# ExpBoard1.net
KiCad netlist of a schematic drawn in EAGLE
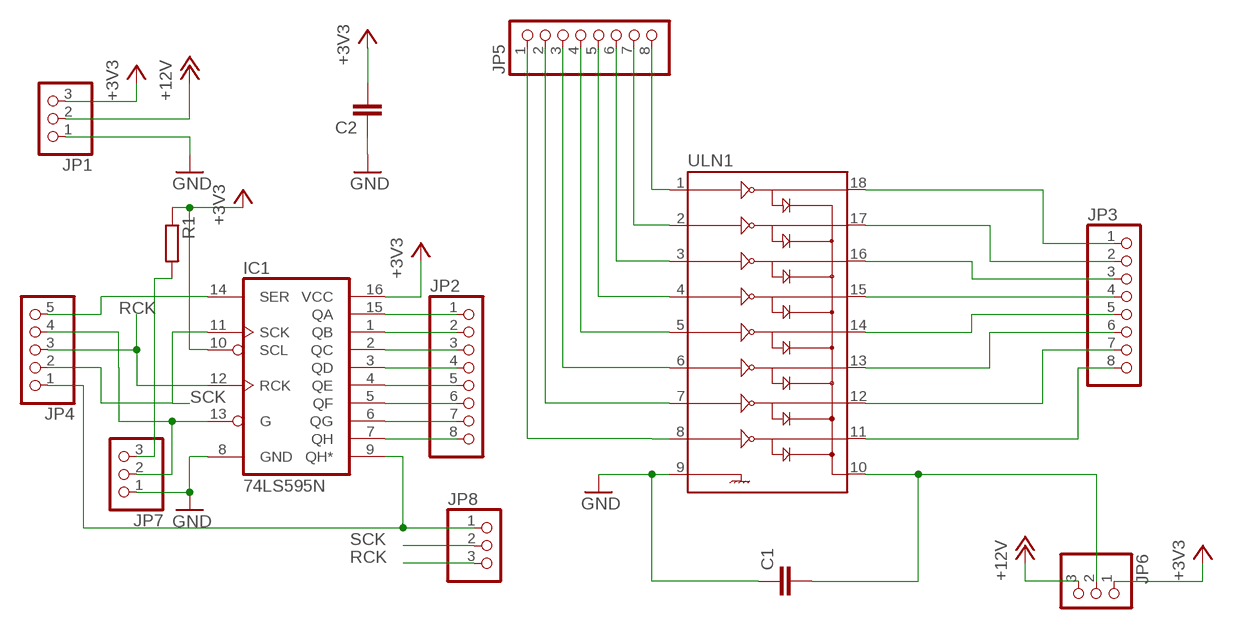
[diagram p0: schematic, sheet 1]

(export (version "E")
  (design (tool "Eeschema 10.0.6"))
  (components
    (comp (ref "C1")
      (value "C-EU050-024X044")
      (footprint "eagle-import:C050-024X044")
      (libsource (lib "eagle-import") (part "C-EU050-024X044"))
    )
    (comp (ref "C2")
      (value "C-EU025-024X044")
      (footprint "eagle-import:C025-024X044")
      (libsource (lib "eagle-import") (part "C-EU025-024X044"))
    )
    (comp (ref "IC1")
      (value "74LS595N")
      (footprint "eagle-import:DIL16")
      (libsource (lib "eagle-import") (part "74595NLS"))
    )
    (comp (ref "JP1")
      (value "PINHD-1X3")
      (footprint "eagle-import:1X03")
      (libsource (lib "eagle-import") (part "PINHD-1X3"))
    )
    (comp (ref "JP2")
      (value "PINHD-1X8")
      (footprint "eagle-import:1X08")
      (libsource (lib "eagle-import") (part "PINHD-1X8"))
    )
    (comp (ref "JP3")
      (value "PINHD-1X8")
      (footprint "eagle-import:1X08")
      (libsource (lib "eagle-import") (part "PINHD-1X8"))
    )
    (comp (ref "JP4")
      (value "PINHD-1X5")
      (footprint "eagle-import:1X05")
      (libsource (lib "eagle-import") (part "PINHD-1X5"))
    )
    (comp (ref "JP5")
      (value "PINHD-1X8")
      (footprint "eagle-import:1X08")
      (libsource (lib "eagle-import") (part "PINHD-1X8"))
    )
    (comp (ref "JP6")
      (value "PINHD-1X3")
      (footprint "eagle-import:1X03")
      (libsource (lib "eagle-import") (part "PINHD-1X3"))
    )
    (comp (ref "JP7")
      (value "PINHD-1X3")
      (footprint "eagle-import:1X03")
      (libsource (lib "eagle-import") (part "PINHD-1X3"))
    )
    (comp (ref "JP8")
      (value "PINHD-1X3")
      (footprint "eagle-import:1X03")
      (libsource (lib "eagle-import") (part "PINHD-1X3"))
    )
    (comp (ref "R1")
      (value "R-EU_0207/12")
      (footprint "eagle-import:0207_12")
      (libsource (lib "eagle-import") (part "R-EU_0207/12"))
    )
    (comp (ref "ULN1")
      (value "ULN2803DIP")
      (footprint "eagle-import:DIL18")
      (libsource (lib "eagle-import") (part "ULN2803DIP"))
    )
  )
  (nets
    (net (code "1") (name "+3V3") (class "Default")
      (node (ref "C2") (pin "2") (pinfunction "2_2") (pintype "passive"))
      (node (ref "IC1") (pin "10") (pinfunction "SCL_10") (pintype "input"))
      (node (ref "IC1") (pin "16") (pinfunction "VCC_16") (pintype "power_in"))
      (node (ref "JP1") (pin "3") (pinfunction "3_3") (pintype "passive"))
      (node (ref "JP6") (pin "1") (pinfunction "1_1") (pintype "passive"))
      (node (ref "R1") (pin "1") (pinfunction "1_1") (pintype "passive"))
    )
    (net (code "2") (name "+12V") (class "Default")
      (node (ref "JP1") (pin "2") (pinfunction "2_2") (pintype "passive"))
      (node (ref "JP6") (pin "3") (pinfunction "3_3") (pintype "passive"))
    )
    (net (code "3") (name "/RCK") (class "Default")
      (node (ref "IC1") (pin "12") (pinfunction "RCK_12") (pintype "input"))
      (node (ref "JP4") (pin "3") (pinfunction "3_3") (pintype "passive"))
      (node (ref "JP8") (pin "3") (pinfunction "3_3") (pintype "passive"))
    )
    (net (code "4") (name "/SCK") (class "Default")
      (node (ref "IC1") (pin "11") (pinfunction "SCK_11") (pintype "input"))
      (node (ref "JP4") (pin "2") (pinfunction "2_2") (pintype "passive"))
      (node (ref "JP8") (pin "2") (pinfunction "2_2") (pintype "passive"))
    )
    (net (code "5") (name "GND") (class "Default")
      (node (ref "C1") (pin "1") (pinfunction "1_1") (pintype "passive"))
      (node (ref "C2") (pin "1") (pinfunction "1_1") (pintype "passive"))
      (node (ref "IC1") (pin "8") (pinfunction "GND_8") (pintype "power_in"))
      (node (ref "JP1") (pin "1") (pinfunction "1_1") (pintype "passive"))
      (node (ref "JP7") (pin "1") (pinfunction "1_1") (pintype "passive"))
      (node (ref "ULN1") (pin "9") (pinfunction "9_9") (pintype "bidirectional"))
    )
    (net (code "6") (name "Net-(C1-Pad2)") (class "Default")
      (node (ref "C1") (pin "2") (pinfunction "2_2") (pintype "passive"))
      (node (ref "JP6") (pin "2") (pinfunction "2_2") (pintype "passive"))
      (node (ref "ULN1") (pin "10") (pinfunction "10_10") (pintype "bidirectional"))
    )
    (net (code "7") (name "Net-(IC1-G)") (class "Default")
      (node (ref "IC1") (pin "13") (pinfunction "G_13") (pintype "input"))
      (node (ref "JP4") (pin "4") (pinfunction "4_4") (pintype "passive"))
      (node (ref "JP7") (pin "2") (pinfunction "2_2") (pintype "passive"))
    )
    (net (code "8") (name "Net-(IC1-QA)") (class "Default")
      (node (ref "IC1") (pin "15") (pinfunction "QA_15") (pintype "tri_state"))
      (node (ref "JP2") (pin "1") (pinfunction "1_1") (pintype "passive"))
    )
    (net (code "9") (name "Net-(IC1-QB)") (class "Default")
      (node (ref "IC1") (pin "1") (pinfunction "QB_1") (pintype "tri_state"))
      (node (ref "JP2") (pin "2") (pinfunction "2_2") (pintype "passive"))
    )
    (net (code "10") (name "Net-(IC1-QC)") (class "Default")
      (node (ref "IC1") (pin "2") (pinfunction "QC_2") (pintype "tri_state"))
      (node (ref "JP2") (pin "3") (pinfunction "3_3") (pintype "passive"))
    )
    (net (code "11") (name "Net-(IC1-QD)") (class "Default")
      (node (ref "IC1") (pin "3") (pinfunction "QD_3") (pintype "tri_state"))
      (node (ref "JP2") (pin "4") (pinfunction "4_4") (pintype "passive"))
    )
    (net (code "12") (name "Net-(IC1-QE)") (class "Default")
      (node (ref "IC1") (pin "4") (pinfunction "QE_4") (pintype "tri_state"))
      (node (ref "JP2") (pin "5") (pinfunction "5_5") (pintype "passive"))
    )
    (net (code "13") (name "Net-(IC1-QF)") (class "Default")
      (node (ref "IC1") (pin "5") (pinfunction "QF_5") (pintype "tri_state"))
      (node (ref "JP2") (pin "6") (pinfunction "6_6") (pintype "passive"))
    )
    (net (code "14") (name "Net-(IC1-QG)") (class "Default")
      (node (ref "IC1") (pin "6") (pinfunction "QG_6") (pintype "tri_state"))
      (node (ref "JP2") (pin "7") (pinfunction "7_7") (pintype "passive"))
    )
    (net (code "15") (name "Net-(IC1-QH)") (class "Default")
      (node (ref "IC1") (pin "7") (pinfunction "QH_7") (pintype "tri_state"))
      (node (ref "JP2") (pin "8") (pinfunction "8_8") (pintype "passive"))
    )
    (net (code "16") (name "Net-(IC1-QH*)") (class "Default")
      (node (ref "IC1") (pin "9") (pinfunction "QH*_9") (pintype "tri_state"))
      (node (ref "JP4") (pin "1") (pinfunction "1_1") (pintype "passive"))
      (node (ref "JP8") (pin "1") (pinfunction "1_1") (pintype "passive"))
    )
    (net (code "17") (name "Net-(IC1-SER)") (class "Default")
      (node (ref "IC1") (pin "14") (pinfunction "SER_14") (pintype "input"))
      (node (ref "JP4") (pin "5") (pinfunction "5_5") (pintype "passive"))
    )
    (net (code "18") (name "Net-(JP3-Pad1)") (class "Default")
      (node (ref "JP3") (pin "1") (pinfunction "1_1") (pintype "passive"))
      (node (ref "ULN1") (pin "18") (pinfunction "18_18") (pintype "bidirectional"))
    )
    (net (code "19") (name "Net-(JP3-Pad2)") (class "Default")
      (node (ref "JP3") (pin "2") (pinfunction "2_2") (pintype "passive"))
      (node (ref "ULN1") (pin "17") (pinfunction "17_17") (pintype "bidirectional"))
    )
    (net (code "20") (name "Net-(JP3-Pad3)") (class "Default")
      (node (ref "JP3") (pin "3") (pinfunction "3_3") (pintype "passive"))
      (node (ref "ULN1") (pin "16") (pinfunction "16_16") (pintype "bidirectional"))
    )
    (net (code "21") (name "Net-(JP3-Pad4)") (class "Default")
      (node (ref "JP3") (pin "4") (pinfunction "4_4") (pintype "passive"))
      (node (ref "ULN1") (pin "15") (pinfunction "15_15") (pintype "bidirectional"))
    )
    (net (code "22") (name "Net-(JP3-Pad5)") (class "Default")
      (node (ref "JP3") (pin "5") (pinfunction "5_5") (pintype "passive"))
      (node (ref "ULN1") (pin "14") (pinfunction "14_14") (pintype "bidirectional"))
    )
    (net (code "23") (name "Net-(JP3-Pad6)") (class "Default")
      (node (ref "JP3") (pin "6") (pinfunction "6_6") (pintype "passive"))
      (node (ref "ULN1") (pin "13") (pinfunction "13_13") (pintype "bidirectional"))
    )
    (net (code "24") (name "Net-(JP3-Pad7)") (class "Default")
      (node (ref "JP3") (pin "7") (pinfunction "7_7") (pintype "passive"))
      (node (ref "ULN1") (pin "12") (pinfunction "12_12") (pintype "bidirectional"))
    )
    (net (code "25") (name "Net-(JP3-Pad8)") (class "Default")
      (node (ref "JP3") (pin "8") (pinfunction "8_8") (pintype "passive"))
      (node (ref "ULN1") (pin "11") (pinfunction "11_11") (pintype "bidirectional"))
    )
    (net (code "26") (name "Net-(JP5-Pad1)") (class "Default")
      (node (ref "JP5") (pin "1") (pinfunction "1_1") (pintype "passive"))
      (node (ref "ULN1") (pin "8") (pinfunction "8_8") (pintype "bidirectional"))
    )
    (net (code "27") (name "Net-(JP5-Pad2)") (class "Default")
      (node (ref "JP5") (pin "2") (pinfunction "2_2") (pintype "passive"))
      (node (ref "ULN1") (pin "7") (pinfunction "7_7") (pintype "bidirectional"))
    )
    (net (code "28") (name "Net-(JP5-Pad3)") (class "Default")
      (node (ref "JP5") (pin "3") (pinfunction "3_3") (pintype "passive"))
      (node (ref "ULN1") (pin "6") (pinfunction "6_6") (pintype "bidirectional"))
    )
    (net (code "29") (name "Net-(JP5-Pad4)") (class "Default")
      (node (ref "JP5") (pin "4") (pinfunction "4_4") (pintype "passive"))
      (node (ref "ULN1") (pin "5") (pinfunction "5_5") (pintype "bidirectional"))
    )
    (net (code "30") (name "Net-(JP5-Pad5)") (class "Default")
      (node (ref "JP5") (pin "5") (pinfunction "5_5") (pintype "passive"))
      (node (ref "ULN1") (pin "4") (pinfunction "4_4") (pintype "bidirectional"))
    )
    (net (code "31") (name "Net-(JP5-Pad6)") (class "Default")
      (node (ref "JP5") (pin "6") (pinfunction "6_6") (pintype "passive"))
      (node (ref "ULN1") (pin "3") (pinfunction "3_3") (pintype "bidirectional"))
    )
    (net (code "32") (name "Net-(JP5-Pad7)") (class "Default")
      (node (ref "JP5") (pin "7") (pinfunction "7_7") (pintype "passive"))
      (node (ref "ULN1") (pin "2") (pinfunction "2_2") (pintype "bidirectional"))
    )
    (net (code "33") (name "Net-(JP5-Pad8)") (class "Default")
      (node (ref "JP5") (pin "8") (pinfunction "8_8") (pintype "passive"))
      (node (ref "ULN1") (pin "1") (pinfunction "1_1") (pintype "bidirectional"))
    )
    (net (code "34") (name "Net-(JP7-Pad3)") (class "Default")
      (node (ref "JP7") (pin "3") (pinfunction "3_3") (pintype "passive"))
      (node (ref "R1") (pin "2") (pinfunction "2_2") (pintype "passive"))
    )
  )
)
